# SSTuino_Evo.net
KiCad netlist of a schematic drawn in EAGLE
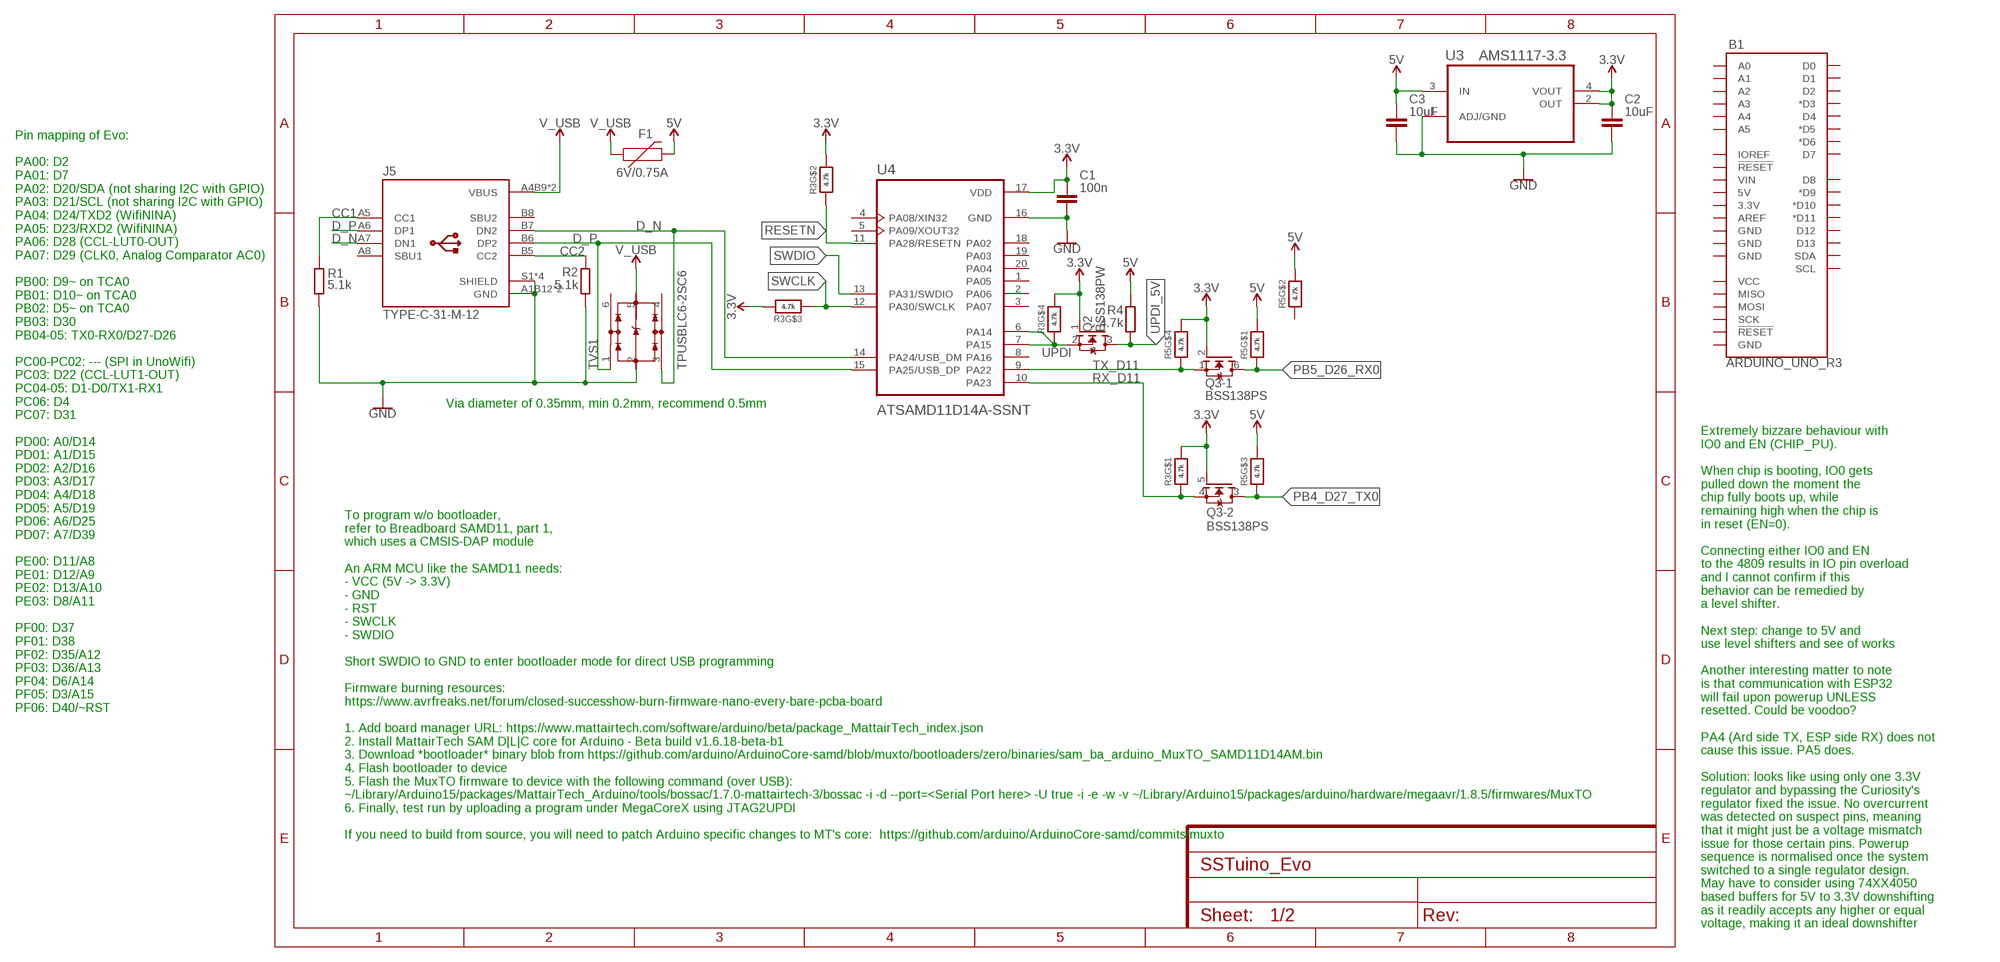
[diagram p0: schematic, sheet 1]
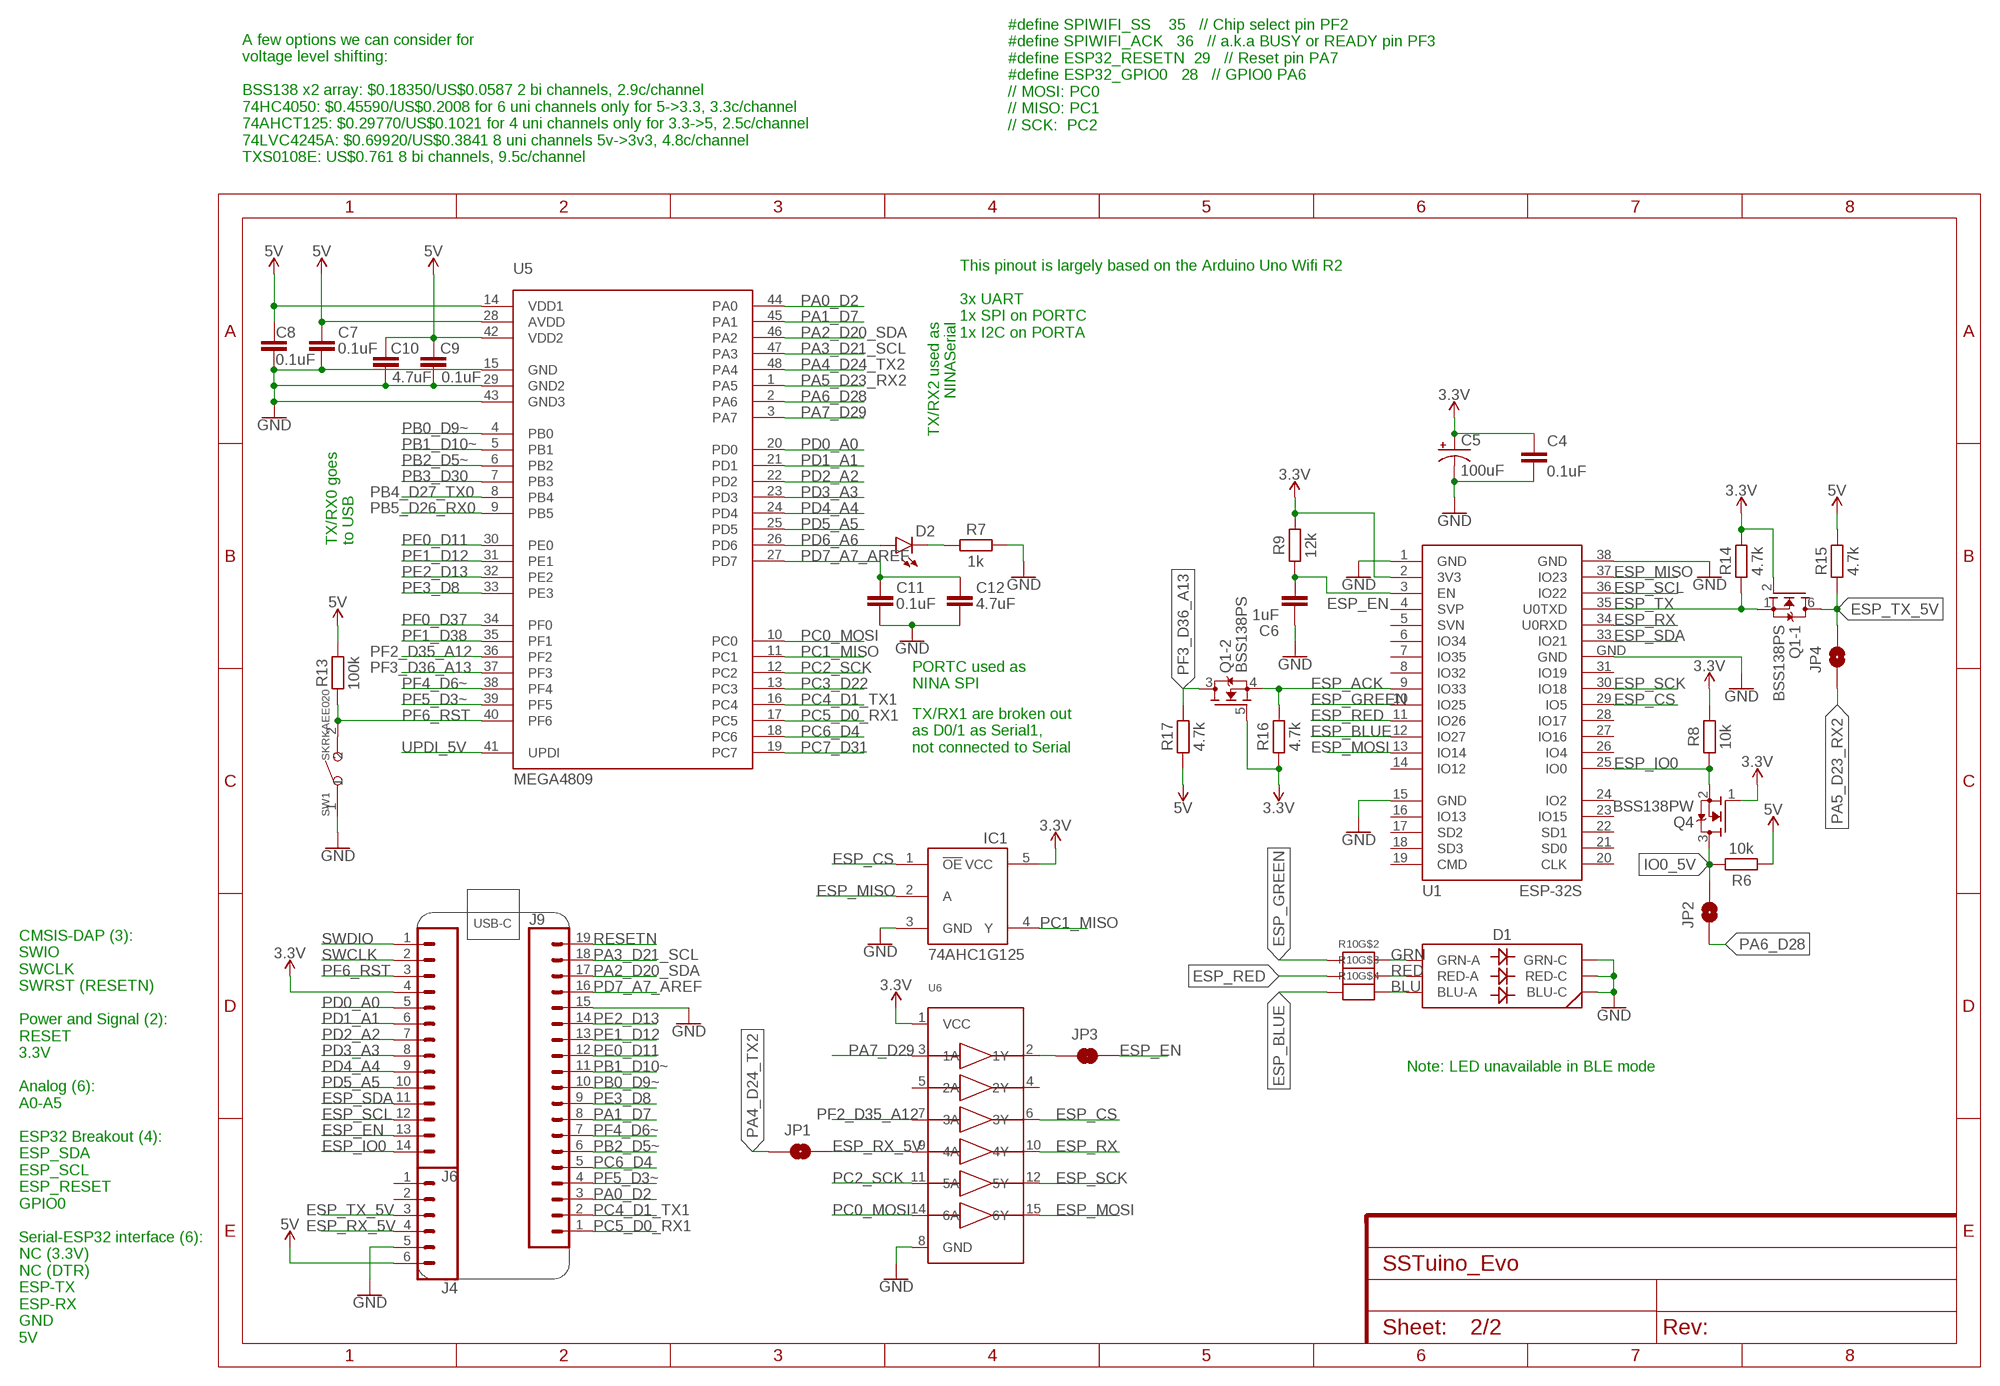
[diagram p1: schematic, sheet 2]

(export (version "E")
  (design (tool "Eeschema 10.0.6"))
  (components
    (comp (ref "B1")
      (value "ARDUINO_UNO_R3")
      (footprint "eagle-import:ARDUINO_R3")
      (libsource (lib "eagle-import") (part "ARDUINO_UNO_R3"))
    )
    (comp (ref "C1")
      (value "100n")
      (footprint "eagle-import:CAPC1005X60")
      (libsource (lib "eagle-import") (part "CCHIP-0402(1005-METRIC)_"))
    )
    (comp (ref "C2")
      (value "10uF")
      (footprint "eagle-import:CAPC1608X85")
      (libsource (lib "eagle-import") (part "CCHIP-0603(1608-METRIC)_"))
    )
    (comp (ref "C3")
      (value "10uF")
      (footprint "eagle-import:CAPC1608X85")
      (libsource (lib "eagle-import") (part "CCHIP-0603(1608-METRIC)_"))
    )
    (comp (ref "F1")
      (value "6V/0.75A")
      (footprint "eagle-import:1206")
      (fields (field (name "LCSC_PART") "C99563"))
      (libsource (lib "eagle-import") (part "PPTC_THREE-QUARTER-AMP"))
    )
    (comp (ref "J5")
      (value "TYPE-C-31-M-12")
      (footprint "eagle-import:HRO_TYPE-C-31-M-12")
      (fields (field (name "MF") "HRO Electronics Co., Ltd.") (field (name "LCSC_PART") "C165948"))
      (libsource (lib "eagle-import") (part "TYPE-C-31-M-12"))
    )
    (comp (ref "Q2")
      (value "BSS138PW")
      (footprint "eagle-import:SOT65P210X110-3N")
      (fields (field (name "MF") "NXP Semiconductors"))
      (libsource (lib "eagle-import") (part "BSS138PW"))
    )
    (comp (ref "Q3")
      (value "BSS138PS")
      (footprint "eagle-import:ARDUINO-TRANSISTORS_SOT363")
      (fields (field (name "MANUFACTURER") "NXP") (field (name "LCSC_PART") "C193381"))
      (libsource (lib "eagle-import") (part "BSS138PS"))
    )
    (comp (ref "R1")
      (value "5.1k")
      (footprint "eagle-import:RESC1005X40")
      (libsource (lib "eagle-import") (part "RCHIP-0402(1005-METRIC)_"))
    )
    (comp (ref "R2")
      (value "5.1k")
      (footprint "eagle-import:RESC1005X40")
      (libsource (lib "eagle-import") (part "RCHIP-0402(1005-METRIC)_"))
    )
    (comp (ref "R3")
      (value "4.7k")
      (footprint "eagle-import:RESPACK_4X0402")
      (fields (field (name "LCSC_PART") "C1980"))
      (libsource (lib "eagle-import") (part "RESISTOR_4PACK0402"))
    )
    (comp (ref "R4")
      (value "4.7k")
      (footprint "eagle-import:RESC1005X40")
      (libsource (lib "eagle-import") (part "RCHIP-0402(1005-METRIC)_"))
    )
    (comp (ref "R5")
      (value "4.7k")
      (footprint "eagle-import:RESPACK_4X0402")
      (fields (field (name "LCSC_PART") "C1980"))
      (libsource (lib "eagle-import") (part "RESISTOR_4PACK0402"))
    )
    (comp (ref "TVS1")
      (value "TPUSBLC6-2SC6")
      (footprint "eagle-import:SOT95P280X110-6N")
      (fields (field (name "LCSC_PART") "C558442"))
      (libsource (lib "eagle-import") (part "TPUSBLC6-2SC6"))
    )
    (comp (ref "U3")
      (value "AMS1117-3.3")
      (footprint "eagle-import:SOT230P696X180-4N")
      (fields (field (name "MPN") "LM1117MP-3.3") (field (name "LCSC_PART") "C6186"))
      (libsource (lib "eagle-import") (part "LM1117MP-3.3"))
    )
    (comp (ref "U4")
      (value "ATSAMD11D14A-SSNT")
      (footprint "eagle-import:SOIC127P1030X265-20N")
      (fields (field (name "MF") "Microchip") (field (name "LCSC_PART") "C2053599"))
      (libsource (lib "eagle-import") (part "ATSAMD11D14A-SSNT"))
    )
    (comp (ref "C4")
      (value "0.1uF")
      (footprint "eagle-import:CAPC1005X60")
      (libsource (lib "eagle-import") (part "CCHIP-0402(1005-METRIC)_"))
    )
    (comp (ref "C5")
      (value "100uF")
      (footprint "eagle-import:CAPMP3216X180N")
      (libsource (lib "eagle-import") (part "C-POL-USTANTALUM-1206(3216-METRIC)_"))
    )
    (comp (ref "C6")
      (value "1uF")
      (footprint "eagle-import:CAPC1005X60")
      (libsource (lib "eagle-import") (part "CCHIP-0402(1005-METRIC)_"))
    )
    (comp (ref "C7")
      (value "0.1uF")
      (footprint "eagle-import:CAPC1005X60")
      (libsource (lib "eagle-import") (part "CCHIP-0402(1005-METRIC)_"))
    )
    (comp (ref "C8")
      (value "0.1uF")
      (footprint "eagle-import:CAPC1005X60")
      (libsource (lib "eagle-import") (part "CCHIP-0402(1005-METRIC)_"))
    )
    (comp (ref "C9")
      (value "0.1uF")
      (footprint "eagle-import:CAPC1005X60")
      (libsource (lib "eagle-import") (part "CCHIP-0402(1005-METRIC)_"))
    )
    (comp (ref "C10")
      (value "4.7uF")
      (footprint "eagle-import:CAPC1005X60")
      (libsource (lib "eagle-import") (part "CCHIP-0402(1005-METRIC)_"))
    )
    (comp (ref "C11")
      (value "0.1uF")
      (footprint "eagle-import:CAPC1005X60")
      (libsource (lib "eagle-import") (part "CCHIP-0402(1005-METRIC)_"))
    )
    (comp (ref "C12")
      (value "4.7uF")
      (footprint "eagle-import:CAPC1005X60")
      (libsource (lib "eagle-import") (part "CCHIP-0402(1005-METRIC)_"))
    )
    (comp (ref "D1")
      (value "LED-RGBTC5050RGBF08")
      (footprint "eagle-import:LED-TRICOLOR-5050")
      (libsource (lib "eagle-import") (part "LED-RGBTC5050RGBF08"))
    )
    (comp (ref "D2")
      (value "LED0603")
      (footprint "eagle-import:LED-0603")
      (libsource (lib "eagle-import") (part "LED0603"))
    )
    (comp (ref "IC1")
      (value "74AHC1G125")
      (footprint "eagle-import:SOT23-5L")
      (fields (field (name "LCSC_PART") "C124295"))
      (libsource (lib "eagle-import") (part "74AHC1G125"))
    )
    (comp (ref "J4")
      (value "CONN_06NO_SILK_FEMALE_PTH")
      (footprint "eagle-import:1X06_NO_SILK")
      (libsource (lib "eagle-import") (part "CONN_06NO_SILK_FEMALE_PTH"))
    )
    (comp (ref "J6")
      (value "CONN_14NO_SILK")
      (footprint "eagle-import:1X14_NO_SILK")
      (libsource (lib "eagle-import") (part "CONN_14NO_SILK"))
    )
    (comp (ref "J9")
      (value "CONN_191X19_NO_SILK")
      (footprint "eagle-import:1X19_NO_SILK")
      (libsource (lib "eagle-import") (part "CONN_191X19_NO_SILK"))
    )
    (comp (ref "JP1")
      (value "JUMPER-SMT_2_NO_SILK")
      (footprint "eagle-import:SMT-JUMPER_2_NO_SILK")
      (libsource (lib "eagle-import") (part "JUMPER-SMT_2_NO_SILK"))
    )
    (comp (ref "JP2")
      (value "JUMPER-SMT_2_NO_SILK")
      (footprint "eagle-import:SMT-JUMPER_2_NO_SILK")
      (libsource (lib "eagle-import") (part "JUMPER-SMT_2_NO_SILK"))
    )
    (comp (ref "JP3")
      (value "JUMPER-SMT_2_NC_TRACE_SILK")
      (footprint "eagle-import:SMT-JUMPER_2_NC_TRACE_SILK")
      (libsource (lib "eagle-import") (part "JUMPER-SMT_2_NC_TRACE_SILK"))
    )
    (comp (ref "JP4")
      (value "JUMPER-SMT_2_NO_SILK")
      (footprint "eagle-import:SMT-JUMPER_2_NO_SILK")
      (libsource (lib "eagle-import") (part "JUMPER-SMT_2_NO_SILK"))
    )
    (comp (ref "Q1")
      (value "BSS138PS")
      (footprint "eagle-import:ARDUINO-TRANSISTORS_SOT363")
      (fields (field (name "MANUFACTURER") "NXP") (field (name "LCSC_PART") "C193381"))
      (libsource (lib "eagle-import") (part "BSS138PS"))
    )
    (comp (ref "Q4")
      (value "BSS138PW")
      (footprint "eagle-import:SOT65P210X110-3N")
      (fields (field (name "MF") "NXP Semiconductors"))
      (libsource (lib "eagle-import") (part "BSS138PW"))
    )
    (comp (ref "R6")
      (value "10k")
      (footprint "eagle-import:RESC1005X40")
      (libsource (lib "eagle-import") (part "RCHIP-0402(1005-METRIC)_"))
    )
    (comp (ref "R7")
      (value "1k")
      (footprint "eagle-import:RESC1005X40")
      (libsource (lib "eagle-import") (part "RCHIP-0402(1005-METRIC)_"))
    )
    (comp (ref "R8")
      (value "10k")
      (footprint "eagle-import:RESC1005X40")
      (libsource (lib "eagle-import") (part "RCHIP-0402(1005-METRIC)_"))
    )
    (comp (ref "R9")
      (value "12k")
      (footprint "eagle-import:RESC1005X40")
      (libsource (lib "eagle-import") (part "RCHIP-0402(1005-METRIC)_"))
    )
    (comp (ref "R10")
      (value "RESISTOR_4PACK0402")
      (footprint "eagle-import:RESPACK_4X0402")
      (libsource (lib "eagle-import") (part "RESISTOR_4PACK0402"))
    )
    (comp (ref "R13")
      (value "100k")
      (footprint "eagle-import:RESC1005X40")
      (libsource (lib "eagle-import") (part "RCHIP-0402(1005-METRIC)_"))
    )
    (comp (ref "R14")
      (value "4.7k")
      (footprint "eagle-import:RESC1005X40")
      (libsource (lib "eagle-import") (part "RCHIP-0402(1005-METRIC)_"))
    )
    (comp (ref "R15")
      (value "4.7k")
      (footprint "eagle-import:RESC1005X40")
      (libsource (lib "eagle-import") (part "RCHIP-0402(1005-METRIC)_"))
    )
    (comp (ref "R16")
      (value "4.7k")
      (footprint "eagle-import:RESC1005X40")
      (libsource (lib "eagle-import") (part "RCHIP-0402(1005-METRIC)_"))
    )
    (comp (ref "R17")
      (value "4.7k")
      (footprint "eagle-import:RESC1005X40")
      (libsource (lib "eagle-import") (part "RCHIP-0402(1005-METRIC)_"))
    )
    (comp (ref "SW1")
      (value "SKRKAEE020")
      (footprint "eagle-import:SW2-2.6-3.9X2.9X1.5+0.4MM")
      (fields (field (name "LCSC_PART") "C115357") (field (name "LCSC_PART_1") "C115357"))
      (libsource (lib "eagle-import") (part "SMD-BUTTON(2P-3.9X2.9X1.5+0.4MM)-SKRKAEE020"))
    )
    (comp (ref "U1")
      (value "ESP-32S")
      (footprint "eagle-import:ESP-32S")
      (libsource (lib "eagle-import") (part "ESP-32S"))
    )
    (comp (ref "U5")
      (value "MEGA4809")
      (footprint "eagle-import:TQFP48")
      (fields (field (name "LCSC_PART") "C189475"))
      (libsource (lib "eagle-import") (part "MEGA4809"))
    )
    (comp (ref "U6")
      (value "74HC4050DTSSOP")
      (footprint "eagle-import:TSSOP16")
      (fields (field (name "LCSC_PART") "C352825"))
      (libsource (lib "eagle-import") (part "74HC4050DTSSOP"))
    )
  )
  (nets
    (net (code "1") (name "3.3V") (class "Default")
      (node (ref "C1") (pin "1") (pinfunction "1_1") (pintype "passive"))
      (node (ref "C2") (pin "1") (pinfunction "1_1") (pintype "passive"))
      (node (ref "C4") (pin "1") (pinfunction "1_1") (pintype "passive"))
      (node (ref "C5") (pin "1") (pinfunction "+_1") (pintype "passive"))
      (node (ref "IC1") (pin "5") (pinfunction "VCC_5") (pintype "power_in"))
      (node (ref "J6") (pin "4") (pinfunction "4_4") (pintype "passive"))
      (node (ref "Q1") (pin "2") (pinfunction "G_2") (pintype "passive"))
      (node (ref "Q1") (pin "5") (pinfunction "G_5") (pintype "passive"))
      (node (ref "Q2") (pin "1") (pinfunction "G_1") (pintype "passive"))
      (node (ref "Q3") (pin "2") (pinfunction "G_2") (pintype "passive"))
      (node (ref "Q3") (pin "5") (pinfunction "G_5") (pintype "passive"))
      (node (ref "Q4") (pin "1") (pinfunction "G_1") (pintype "passive"))
      (node (ref "R14") (pin "2") (pinfunction "2_2") (pintype "passive"))
      (node (ref "R16") (pin "1") (pinfunction "1_1") (pintype "passive"))
      (node (ref "R3") (pin "5") (pinfunction "2_5") (pintype "passive"))
      (node (ref "R3") (pin "6") (pinfunction "2_6") (pintype "passive"))
      (node (ref "R3") (pin "7") (pinfunction "2_7") (pintype "passive"))
      (node (ref "R3") (pin "8") (pinfunction "2_8") (pintype "passive"))
      (node (ref "R5") (pin "5") (pinfunction "2_5") (pintype "passive"))
      (node (ref "R8") (pin "2") (pinfunction "2_2") (pintype "passive"))
      (node (ref "R9") (pin "2") (pinfunction "2_2") (pintype "passive"))
      (node (ref "U1") (pin "2") (pinfunction "3V3_2") (pintype "power_in"))
      (node (ref "U3") (pin "2") (pinfunction "OUT_2") (pintype "output"))
      (node (ref "U3") (pin "4") (pinfunction "VOUT_4") (pintype "output"))
      (node (ref "U4") (pin "17") (pinfunction "VDD_17") (pintype "power_in"))
      (node (ref "U6") (pin "1") (pinfunction "VCC_1") (pintype "bidirectional"))
    )
    (net (code "2") (name "5V") (class "Default")
      (node (ref "C10") (pin "1") (pinfunction "1_1") (pintype "passive"))
      (node (ref "C3") (pin "1") (pinfunction "1_1") (pintype "passive"))
      (node (ref "C7") (pin "1") (pinfunction "1_1") (pintype "passive"))
      (node (ref "C8") (pin "1") (pinfunction "1_1") (pintype "passive"))
      (node (ref "C9") (pin "1") (pinfunction "1_1") (pintype "passive"))
      (node (ref "F1") (pin "2") (pinfunction "2_2") (pintype "bidirectional"))
      (node (ref "J4") (pin "6") (pinfunction "6_6") (pintype "passive"))
      (node (ref "R13") (pin "2") (pinfunction "2_2") (pintype "passive"))
      (node (ref "R15") (pin "2") (pinfunction "2_2") (pintype "passive"))
      (node (ref "R17") (pin "1") (pinfunction "1_1") (pintype "passive"))
      (node (ref "R4") (pin "2") (pinfunction "2_2") (pintype "passive"))
      (node (ref "R5") (pin "6") (pinfunction "2_6") (pintype "passive"))
      (node (ref "R5") (pin "7") (pinfunction "2_7") (pintype "passive"))
      (node (ref "R5") (pin "8") (pinfunction "2_8") (pintype "passive"))
      (node (ref "R6") (pin "1") (pinfunction "1_1") (pintype "passive"))
      (node (ref "U3") (pin "3") (pinfunction "IN_3") (pintype "input"))
      (node (ref "U5") (pin "14") (pinfunction "VDD1_14") (pintype "bidirectional"))
      (node (ref "U5") (pin "28") (pinfunction "AVDD_28") (pintype "bidirectional"))
      (node (ref "U5") (pin "42") (pinfunction "VDD2_42") (pintype "bidirectional"))
    )
    (net (code "3") (name "BLU") (class "Default")
      (node (ref "D1") (pin "6") (pinfunction "BLU-A_6") (pintype "bidirectional"))
      (node (ref "R10") (pin "5") (pinfunction "2_5") (pintype "passive"))
    )
    (net (code "4") (name "CC1") (class "Default")
      (node (ref "J5") (pin "A5") (pinfunction "CC1_A5") (pintype "bidirectional"))
      (node (ref "R1") (pin "1") (pinfunction "1_1") (pintype "passive"))
    )
    (net (code "5") (name "CC2") (class "Default")
      (node (ref "J5") (pin "B5") (pinfunction "CC2_B5") (pintype "bidirectional"))
      (node (ref "R2") (pin "2") (pinfunction "2_2") (pintype "passive"))
    )
    (net (code "6") (name "D_N") (class "Default")
      (node (ref "J5") (pin "A7") (pinfunction "DN1_A7") (pintype "bidirectional"))
      (node (ref "J5") (pin "B7") (pinfunction "DN2_B7") (pintype "bidirectional"))
      (node (ref "TVS1") (pin "3") (pinfunction "IO2_3") (pintype "passive"))
      (node (ref "U4") (pin "14") (pinfunction "PA24/USB_DM_14") (pintype "bidirectional"))
    )
    (net (code "7") (name "D_P") (class "Default")
      (node (ref "J5") (pin "A6") (pinfunction "DP1_A6") (pintype "bidirectional"))
      (node (ref "J5") (pin "B6") (pinfunction "DP2_B6") (pintype "bidirectional"))
      (node (ref "TVS1") (pin "1") (pinfunction "IO1_1") (pintype "passive"))
      (node (ref "U4") (pin "15") (pinfunction "PA25/USB_DP_15") (pintype "bidirectional"))
    )
    (net (code "8") (name "ESP_ACK") (class "Default")
      (node (ref "Q1") (pin "4") (pinfunction "S_4") (pintype "passive"))
      (node (ref "R16") (pin "2") (pinfunction "2_2") (pintype "passive"))
      (node (ref "U1") (pin "9") (pinfunction "IO33_9") (pintype "bidirectional"))
    )
    (net (code "9") (name "ESP_BLUE") (class "Default")
      (node (ref "R10") (pin "4") (pinfunction "1_4") (pintype "passive"))
      (node (ref "U1") (pin "12") (pinfunction "IO27_12") (pintype "bidirectional"))
    )
    (net (code "10") (name "ESP_CS") (class "Default")
      (node (ref "IC1") (pin "1") (pinfunction "~{OE}_1") (pintype "input"))
      (node (ref "U1") (pin "29") (pinfunction "IO5_29") (pintype "bidirectional"))
      (node (ref "U6") (pin "6") (pinfunction "3Y_6") (pintype "bidirectional"))
    )
    (net (code "11") (name "ESP_EN") (class "Default")
      (node (ref "C6") (pin "2") (pinfunction "2_2") (pintype "passive"))
      (node (ref "J6") (pin "13") (pinfunction "13_13") (pintype "passive"))
      (node (ref "JP3") (pin "2") (pinfunction "2_2") (pintype "passive"))
      (node (ref "R9") (pin "1") (pinfunction "1_1") (pintype "passive"))
      (node (ref "U1") (pin "3") (pinfunction "EN_3") (pintype "input"))
    )
    (net (code "12") (name "ESP_GREEN") (class "Default")
      (node (ref "R10") (pin "2") (pinfunction "1_2") (pintype "passive"))
      (node (ref "U1") (pin "10") (pinfunction "IO25_10") (pintype "bidirectional"))
    )
    (net (code "13") (name "ESP_IO0") (class "Default")
      (node (ref "J6") (pin "14") (pinfunction "14_14") (pintype "passive"))
      (node (ref "Q4") (pin "2") (pinfunction "S_2") (pintype "passive"))
      (node (ref "R8") (pin "1") (pinfunction "1_1") (pintype "passive"))
      (node (ref "U1") (pin "25") (pinfunction "IO0_25") (pintype "bidirectional"))
    )
    (net (code "14") (name "ESP_MISO") (class "Default")
      (node (ref "IC1") (pin "2") (pinfunction "A_2") (pintype "input"))
      (node (ref "U1") (pin "37") (pinfunction "IO23_37") (pintype "bidirectional"))
    )
    (net (code "15") (name "ESP_MOSI") (class "Default")
      (node (ref "U1") (pin "13") (pinfunction "IO14_13") (pintype "bidirectional"))
      (node (ref "U6") (pin "15") (pinfunction "6Y_15") (pintype "bidirectional"))
    )
    (net (code "16") (name "ESP_RED") (class "Default")
      (node (ref "R10") (pin "3") (pinfunction "1_3") (pintype "passive"))
      (node (ref "U1") (pin "11") (pinfunction "IO26_11") (pintype "bidirectional"))
    )
    (net (code "17") (name "ESP_RX") (class "Default")
      (node (ref "U1") (pin "34") (pinfunction "U0RXD_34") (pintype "bidirectional"))
      (node (ref "U6") (pin "10") (pinfunction "4Y_10") (pintype "bidirectional"))
    )
    (net (code "18") (name "ESP_RX_5V") (class "Default")
      (node (ref "J4") (pin "4") (pinfunction "4_4") (pintype "passive"))
      (node (ref "JP1") (pin "2") (pinfunction "2_2") (pintype "passive"))
      (node (ref "U6") (pin "9") (pinfunction "4A_9") (pintype "bidirectional"))
    )
    (net (code "19") (name "ESP_SCK") (class "Default")
      (node (ref "U1") (pin "30") (pinfunction "IO18_30") (pintype "bidirectional"))
      (node (ref "U6") (pin "12") (pinfunction "5Y_12") (pintype "bidirectional"))
    )
    (net (code "20") (name "ESP_SCL") (class "Default")
      (node (ref "J6") (pin "12") (pinfunction "12_12") (pintype "passive"))
      (node (ref "U1") (pin "36") (pinfunction "IO22_36") (pintype "bidirectional"))
    )
    (net (code "21") (name "ESP_SDA") (class "Default")
      (node (ref "J6") (pin "11") (pinfunction "11_11") (pintype "passive"))
      (node (ref "U1") (pin "33") (pinfunction "IO21_33") (pintype "bidirectional"))
    )
    (net (code "22") (name "ESP_TX") (class "Default")
      (node (ref "Q1") (pin "1") (pinfunction "S_1") (pintype "passive"))
      (node (ref "R14") (pin "1") (pinfunction "1_1") (pintype "passive"))
      (node (ref "U1") (pin "35") (pinfunction "U0TXD_35") (pintype "bidirectional"))
    )
    (net (code "23") (name "ESP_TX_5V") (class "Default")
      (node (ref "J4") (pin "3") (pinfunction "3_3") (pintype "passive"))
      (node (ref "JP4") (pin "2") (pinfunction "2_2") (pintype "passive"))
      (node (ref "Q1") (pin "6") (pinfunction "D_6") (pintype "passive"))
      (node (ref "R15") (pin "1") (pinfunction "1_1") (pintype "passive"))
    )
    (net (code "24") (name "GND") (class "Default")
      (node (ref "C1") (pin "2") (pinfunction "2_2") (pintype "passive"))
      (node (ref "C10") (pin "2") (pinfunction "2_2") (pintype "passive"))
      (node (ref "C11") (pin "2") (pinfunction "2_2") (pintype "passive"))
      (node (ref "C12") (pin "2") (pinfunction "2_2") (pintype "passive"))
      (node (ref "C2") (pin "2") (pinfunction "2_2") (pintype "passive"))
      (node (ref "C3") (pin "2") (pinfunction "2_2") (pintype "passive"))
      (node (ref "C4") (pin "2") (pinfunction "2_2") (pintype "passive"))
      (node (ref "C5") (pin "2") (pinfunction "-_2") (pintype "passive"))
      (node (ref "C6") (pin "1") (pinfunction "1_1") (pintype "passive"))
      (node (ref "C7") (pin "2") (pinfunction "2_2") (pintype "passive"))
      (node (ref "C8") (pin "2") (pinfunction "2_2") (pintype "passive"))
      (node (ref "C9") (pin "2") (pinfunction "2_2") (pintype "passive"))
      (node (ref "D1") (pin "1") (pinfunction "BLU-C_1") (pintype "bidirectional"))
      (node (ref "D1") (pin "2") (pinfunction "RED-C_2") (pintype "bidirectional"))
      (node (ref "D1") (pin "3") (pinfunction "GRN-C_3") (pintype "bidirectional"))
      (node (ref "IC1") (pin "3") (pinfunction "GND_3") (pintype "power_in"))
      (node (ref "J4") (pin "5") (pinfunction "5_5") (pintype "passive"))
      (node (ref "J5") (pin "A1B12") (pinfunction "GND_A1B12") (pintype "power_in"))
      (node (ref "J5") (pin "B1A12") (pinfunction "GND_B1A12") (pintype "power_in"))
      (node (ref "J5") (pin "S1") (pinfunction "SHIELD_S1") (pintype "passive"))
      (node (ref "J5") (pin "S2") (pinfunction "SHIELD_S2") (pintype "passive"))
      (node (ref "J5") (pin "S3") (pinfunction "SHIELD_S3") (pintype "passive"))
      (node (ref "J5") (pin "S4") (pinfunction "SHIELD_S4") (pintype "passive"))
      (node (ref "J9") (pin "15") (pinfunction "15_15") (pintype "passive"))
      (node (ref "R1") (pin "2") (pinfunction "2_2") (pintype "passive"))
      (node (ref "R2") (pin "1") (pinfunction "1_1") (pintype "passive"))
      (node (ref "R7") (pin "2") (pinfunction "2_2") (pintype "passive"))
      (node (ref "SW1") (pin "1") (pinfunction "1_1") (pintype "bidirectional"))
      (node (ref "TVS1") (pin "2") (pinfunction "VSS_2") (pintype "power_in"))
      (node (ref "U1") (pin "1") (pinfunction "GND_1") (pintype "power_in"))
      (node (ref "U1") (pin "15") (pinfunction "GND_15") (pintype "power_in"))
      (node (ref "U1") (pin "38") (pinfunction "GND_38") (pintype "power_in"))
      (node (ref "U1") (pin "GND") (pinfunction "GND_GND") (pintype "power_in"))
      (node (ref "U3") (pin "1") (pinfunction "ADJ/GND_1") (pintype "passive"))
      (node (ref "U4") (pin "16") (pinfunction "GND_16") (pintype "power_in"))
      (node (ref "U5") (pin "15") (pinfunction "GND_15") (pintype "bidirectional"))
      (node (ref "U5") (pin "29") (pinfunction "GND2_29") (pintype "bidirectional"))
      (node (ref "U5") (pin "43") (pinfunction "GND3_43") (pintype "bidirectional"))
      (node (ref "U6") (pin "8") (pinfunction "GND_8") (pintype "bidirectional"))
    )
    (net (code "25") (name "GRN") (class "Default")
      (node (ref "D1") (pin "4") (pinfunction "GRN-A_4") (pintype "bidirectional"))
      (node (ref "R10") (pin "7") (pinfunction "2_7") (pintype "passive"))
    )
    (net (code "26") (name "IO0_5V") (class "Default")
      (node (ref "JP2") (pin "2") (pinfunction "2_2") (pintype "passive"))
      (node (ref "Q4") (pin "3") (pinfunction "D_3") (pintype "passive"))
      (node (ref "R6") (pin "2") (pinfunction "2_2") (pintype "passive"))
    )
    (net (code "27") (name "Net-(D2-PadC)") (class "Default")
      (node (ref "D2") (pin "C") (pinfunction "C_C") (pintype "passive"))
      (node (ref "R7") (pin "1") (pinfunction "1_1") (pintype "passive"))
    )
    (net (code "28") (name "Net-(U6-1Y)") (class "Default")
      (node (ref "JP3") (pin "1") (pinfunction "1_1") (pintype "passive"))
      (node (ref "U6") (pin "2") (pinfunction "1Y_2") (pintype "bidirectional"))
    )
    (net (code "29") (name "PA0_D2") (class "Default")
      (node (ref "J9") (pin "3") (pinfunction "3_3") (pintype "passive"))
      (node (ref "U5") (pin "44") (pinfunction "PA0_44") (pintype "bidirectional"))
    )
    (net (code "30") (name "PA1_D7") (class "Default")
      (node (ref "J9") (pin "8") (pinfunction "8_8") (pintype "passive"))
      (node (ref "U5") (pin "45") (pinfunction "PA1_45") (pintype "bidirectional"))
    )
    (net (code "31") (name "PA2_D20_SDA") (class "Default")
      (node (ref "J9") (pin "17") (pinfunction "17_17") (pintype "passive"))
      (node (ref "U5") (pin "46") (pinfunction "PA2_46") (pintype "bidirectional"))
    )
    (net (code "32") (name "PA3_D21_SCL") (class "Default")
      (node (ref "J9") (pin "18") (pinfunction "18_18") (pintype "passive"))
      (node (ref "U5") (pin "47") (pinfunction "PA3_47") (pintype "bidirectional"))
    )
    (net (code "33") (name "PA4_D24_TX2") (class "Default")
      (node (ref "JP1") (pin "1") (pinfunction "1_1") (pintype "passive"))
      (node (ref "U5") (pin "48") (pinfunction "PA4_48") (pintype "bidirectional"))
    )
    (net (code "34") (name "PA5_D23_RX2") (class "Default")
      (node (ref "JP4") (pin "1") (pinfunction "1_1") (pintype "passive"))
      (node (ref "U5") (pin "1") (pinfunction "PA5_1") (pintype "bidirectional"))
    )
    (net (code "35") (name "PA6_D28") (class "Default")
      (node (ref "JP2") (pin "1") (pinfunction "1_1") (pintype "passive"))
      (node (ref "U5") (pin "2") (pinfunction "PA6_2") (pintype "bidirectional"))
    )
    (net (code "36") (name "PA7_D29") (class "Default")
      (node (ref "U5") (pin "3") (pinfunction "PA7_3") (pintype "bidirectional"))
      (node (ref "U6") (pin "3") (pinfunction "1A_3") (pintype "bidirectional"))
    )
    (net (code "37") (name "PB0_D9~{}") (class "Default")
      (node (ref "J9") (pin "10") (pinfunction "10_10") (pintype "passive"))
      (node (ref "U5") (pin "4") (pinfunction "PB0_4") (pintype "bidirectional"))
    )
    (net (code "38") (name "PB1_D10~{}") (class "Default")
      (node (ref "J9") (pin "11") (pinfunction "11_11") (pintype "passive"))
      (node (ref "U5") (pin "5") (pinfunction "PB1_5") (pintype "bidirectional"))
    )
    (net (code "39") (name "PB2_D5~{}") (class "Default")
      (node (ref "J9") (pin "6") (pinfunction "6_6") (pintype "passive"))
      (node (ref "U5") (pin "6") (pinfunction "PB2_6") (pintype "bidirectional"))
    )
    (net (code "40") (name "PB3_D30") (class "Default")
      (node (ref "U5") (pin "7") (pinfunction "PB3_7") (pintype "bidirectional"))
    )
    (net (code "41") (name "PB4_D27_TX0") (class "Default")
      (node (ref "Q3") (pin "3") (pinfunction "D_3") (pintype "passive"))
      (node (ref "R5") (pin "3") (pinfunction "1_3") (pintype "passive"))
      (node (ref "U5") (pin "8") (pinfunction "PB4_8") (pintype "bidirectional"))
    )
    (net (code "42") (name "PB5_D26_RX0") (class "Default")
      (node (ref "Q3") (pin "6") (pinfunction "D_6") (pintype "passive"))
      (node (ref "R5") (pin "1") (pinfunction "1_1") (pintype "passive"))
      (node (ref "U5") (pin "9") (pinfunction "PB5_9") (pintype "bidirectional"))
    )
    (net (code "43") (name "PC0_MOSI") (class "Default")
      (node (ref "U5") (pin "10") (pinfunction "PC0_10") (pintype "bidirectional"))
      (node (ref "U6") (pin "14") (pinfunction "6A_14") (pintype "bidirectional"))
    )
    (net (code "44") (name "PC1_MISO") (class "Default")
      (node (ref "IC1") (pin "4") (pinfunction "Y_4") (pintype "output"))
      (node (ref "U5") (pin "11") (pinfunction "PC1_11") (pintype "bidirectional"))
    )
    (net (code "45") (name "PC2_SCK") (class "Default")
      (node (ref "U5") (pin "12") (pinfunction "PC2_12") (pintype "bidirectional"))
      (node (ref "U6") (pin "11") (pinfunction "5A_11") (pintype "bidirectional"))
    )
    (net (code "46") (name "PC3_D22") (class "Default")
      (node (ref "U5") (pin "13") (pinfunction "PC3_13") (pintype "bidirectional"))
    )
    (net (code "47") (name "PC4_D1_TX1") (class "Default")
      (node (ref "J9") (pin "2") (pinfunction "2_2") (pintype "passive"))
      (node (ref "U5") (pin "16") (pinfunction "PC4_16") (pintype "bidirectional"))
    )
    (net (code "48") (name "PC5_D0_RX1") (class "Default")
      (node (ref "J9") (pin "1") (pinfunction "1_1") (pintype "passive"))
      (node (ref "U5") (pin "17") (pinfunction "PC5_17") (pintype "bidirectional"))
    )
    (net (code "49") (name "PC6_D4") (class "Default")
      (node (ref "J9") (pin "5") (pinfunction "5_5") (pintype "passive"))
      (node (ref "U5") (pin "18") (pinfunction "PC6_18") (pintype "bidirectional"))
    )
    (net (code "50") (name "PC7_D31") (class "Default")
      (node (ref "U5") (pin "19") (pinfunction "PC7_19") (pintype "bidirectional"))
    )
    (net (code "51") (name "PD0_A0") (class "Default")
      (node (ref "J6") (pin "5") (pinfunction "5_5") (pintype "passive"))
      (node (ref "U5") (pin "20") (pinfunction "PD0_20") (pintype "bidirectional"))
    )
    (net (code "52") (name "PD1_A1") (class "Default")
      (node (ref "J6") (pin "6") (pinfunction "6_6") (pintype "passive"))
      (node (ref "U5") (pin "21") (pinfunction "PD1_21") (pintype "bidirectional"))
    )
    (net (code "53") (name "PD2_A2") (class "Default")
      (node (ref "J6") (pin "7") (pinfunction "7_7") (pintype "passive"))
      (node (ref "U5") (pin "22") (pinfunction "PD2_22") (pintype "bidirectional"))
    )
    (net (code "54") (name "PD3_A3") (class "Default")
      (node (ref "J6") (pin "8") (pinfunction "8_8") (pintype "passive"))
      (node (ref "U5") (pin "23") (pinfunction "PD3_23") (pintype "bidirectional"))
    )
    (net (code "55") (name "PD4_A4") (class "Default")
      (node (ref "J6") (pin "9") (pinfunction "9_9") (pintype "passive"))
      (node (ref "U5") (pin "24") (pinfunction "PD4_24") (pintype "bidirectional"))
    )
    (net (code "56") (name "PD5_A5") (class "Default")
      (node (ref "J6") (pin "10") (pinfunction "10_10") (pintype "passive"))
      (node (ref "U5") (pin "25") (pinfunction "PD5_25") (pintype "bidirectional"))
    )
    (net (code "57") (name "PD6_A6") (class "Default")
      (node (ref "D2") (pin "A") (pinfunction "A_A") (pintype "passive"))
      (node (ref "U5") (pin "26") (pinfunction "PD6_26") (pintype "bidirectional"))
    )
    (net (code "58") (name "PD7_A7_AREF") (class "Default")
      (node (ref "C11") (pin "1") (pinfunction "1_1") (pintype "passive"))
      (node (ref "C12") (pin "1") (pinfunction "1_1") (pintype "passive"))
      (node (ref "J9") (pin "16") (pinfunction "16_16") (pintype "passive"))
      (node (ref "U5") (pin "27") (pinfunction "PD7_27") (pintype "bidirectional"))
    )
    (net (code "59") (name "PE0_D11") (class "Default")
      (node (ref "J9") (pin "12") (pinfunction "12_12") (pintype "passive"))
      (node (ref "U5") (pin "30") (pinfunction "PE0_30") (pintype "bidirectional"))
    )
    (net (code "60") (name "PE1_D12") (class "Default")
      (node (ref "J9") (pin "13") (pinfunction "13_13") (pintype "passive"))
      (node (ref "U5") (pin "31") (pinfunction "PE1_31") (pintype "bidirectional"))
    )
    (net (code "61") (name "PE2_D13") (class "Default")
      (node (ref "J9") (pin "14") (pinfunction "14_14") (pintype "passive"))
      (node (ref "U5") (pin "32") (pinfunction "PE2_32") (pintype "bidirectional"))
    )
    (net (code "62") (name "PE3_D8") (class "Default")
      (node (ref "J9") (pin "9") (pinfunction "9_9") (pintype "passive"))
      (node (ref "U5") (pin "33") (pinfunction "PE3_33") (pintype "bidirectional"))
    )
    (net (code "63") (name "PF0_D37") (class "Default")
      (node (ref "U5") (pin "34") (pinfunction "PF0_34") (pintype "bidirectional"))
    )
    (net (code "64") (name "PF1_D38") (class "Default")
      (node (ref "U5") (pin "35") (pinfunction "PF1_35") (pintype "bidirectional"))
    )
    (net (code "65") (name "PF2_D35_A12") (class "Default")
      (node (ref "U5") (pin "36") (pinfunction "PF2_36") (pintype "bidirectional"))
      (node (ref "U6") (pin "7") (pinfunction "3A_7") (pintype "bidirectional"))
    )
    (net (code "66") (name "PF3_D36_A13") (class "Default")
      (node (ref "Q1") (pin "3") (pinfunction "D_3") (pintype "passive"))
      (node (ref "R17") (pin "2") (pinfunction "2_2") (pintype "passive"))
      (node (ref "U5") (pin "37") (pinfunction "PF3_37") (pintype "bidirectional"))
    )
    (net (code "67") (name "PF4_D6~{}") (class "Default")
      (node (ref "J9") (pin "7") (pinfunction "7_7") (pintype "passive"))
      (node (ref "U5") (pin "38") (pinfunction "PF4_38") (pintype "bidirectional"))
    )
    (net (code "68") (name "PF5_D3~{}") (class "Default")
      (node (ref "J9") (pin "4") (pinfunction "4_4") (pintype "passive"))
      (node (ref "U5") (pin "39") (pinfunction "PF5_39") (pintype "bidirectional"))
    )
    (net (code "69") (name "PF6_RST") (class "Default")
      (node (ref "J6") (pin "3") (pinfunction "3_3") (pintype "passive"))
      (node (ref "R13") (pin "1") (pinfunction "1_1") (pintype "passive"))
      (node (ref "SW1") (pin "2") (pinfunction "2_2") (pintype "bidirectional"))
      (node (ref "U5") (pin "40") (pinfunction "PF6_40") (pintype "bidirectional"))
    )
    (net (code "70") (name "RED") (class "Default")
      (node (ref "D1") (pin "5") (pinfunction "RED-A_5") (pintype "bidirectional"))
      (node (ref "R10") (pin "6") (pinfunction "2_6") (pintype "passive"))
    )
    (net (code "71") (name "RESETN") (class "Default")
      (node (ref "J9") (pin "19") (pinfunction "19_19") (pintype "passive"))
      (node (ref "R3") (pin "2") (pinfunction "1_2") (pintype "passive"))
      (node (ref "U4") (pin "11") (pinfunction "PA28/RESETN_11") (pintype "input"))
    )
    (net (code "72") (name "RX_D11") (class "Default")
      (node (ref "Q3") (pin "4") (pinfunction "S_4") (pintype "passive"))
      (node (ref "R3") (pin "1") (pinfunction "1_1") (pintype "passive"))
      (node (ref "U4") (pin "10") (pinfunction "PA23_10") (pintype "bidirectional"))
    )
    (net (code "73") (name "SWCLK") (class "Default")
      (node (ref "J6") (pin "2") (pinfunction "2_2") (pintype "passive"))
      (node (ref "R3") (pin "3") (pinfunction "1_3") (pintype "passive"))
      (node (ref "U4") (pin "12") (pinfunction "PA30/SWCLK_12") (pintype "bidirectional"))
    )
    (net (code "74") (name "SWDIO") (class "Default")
      (node (ref "J6") (pin "1") (pinfunction "1_1") (pintype "passive"))
      (node (ref "U4") (pin "13") (pinfunction "PA31/SWDIO_13") (pintype "bidirectional"))
    )
    (net (code "75") (name "TX_D11") (class "Default")
      (node (ref "Q3") (pin "1") (pinfunction "S_1") (pintype "passive"))
      (node (ref "R5") (pin "4") (pinfunction "1_4") (pintype "passive"))
      (node (ref "U4") (pin "9") (pinfunction "PA22_9") (pintype "bidirectional"))
    )
    (net (code "76") (name "UPDI") (class "Default")
      (node (ref "Q2") (pin "2") (pinfunction "S_2") (pintype "passive"))
      (node (ref "R3") (pin "4") (pinfunction "1_4") (pintype "passive"))
      (node (ref "U4") (pin "6") (pinfunction "PA14_6") (pintype "bidirectional"))
      (node (ref "U4") (pin "7") (pinfunction "PA15_7") (pintype "bidirectional"))
    )
    (net (code "77") (name "UPDI_5V") (class "Default")
      (node (ref "Q2") (pin "3") (pinfunction "D_3") (pintype "passive"))
      (node (ref "R4") (pin "1") (pinfunction "1_1") (pintype "passive"))
      (node (ref "U5") (pin "41") (pinfunction "UPDI_41") (pintype "bidirectional"))
    )
    (net (code "78") (name "V_USB") (class "Default")
      (node (ref "F1") (pin "1") (pinfunction "1_1") (pintype "bidirectional"))
      (node (ref "J5") (pin "A4B9") (pinfunction "VBUS_A4B9") (pintype "power_in"))
      (node (ref "J5") (pin "B4A9") (pinfunction "VBUS_B4A9") (pintype "power_in"))
      (node (ref "TVS1") (pin "5") (pinfunction "VCC_5") (pintype "power_in"))
    )
    (net (code "79") (name "unconnected-(B1-*D3-PadD3)") (class "Default")
      (node (ref "B1") (pin "D3") (pinfunction "*D3_D3") (pintype "bidirectional"))
    )
    (net (code "80") (name "unconnected-(B1-*D5-PadD5)") (class "Default")
      (node (ref "B1") (pin "D5") (pinfunction "*D5_D5") (pintype "bidirectional"))
    )
    (net (code "81") (name "unconnected-(B1-*D6-PadD6)") (class "Default")
      (node (ref "B1") (pin "D6") (pinfunction "*D6_D6") (pintype "bidirectional"))
    )
    (net (code "82") (name "unconnected-(B1-*D9-PadD9)") (class "Default")
      (node (ref "B1") (pin "D9") (pinfunction "*D9_D9") (pintype "bidirectional"))
    )
    (net (code "83") (name "unconnected-(B1-*D10-PadD10)") (class "Default")
      (node (ref "B1") (pin "D10") (pinfunction "*D10_D10") (pintype "bidirectional"))
    )
    (net (code "84") (name "unconnected-(B1-*D11-PadD11)") (class "Default")
      (node (ref "B1") (pin "D11") (pinfunction "*D11_D11") (pintype "bidirectional"))
    )
    (net (code "85") (name "unconnected-(B1-GND-PadGND@1)") (class "Default")
      (node (ref "B1") (pin "GND@1") (pinfunction "GND_GND@1") (pintype "bidirectional"))
    )
    (net (code "86") (name "unconnected-(B1-GND-PadGND@2)") (class "Default")
      (node (ref "B1") (pin "GND@2") (pinfunction "GND_GND@2") (pintype "bidirectional"))
    )
    (net (code "87") (name "unconnected-(B1-GND-PadGND@3)") (class "Default")
      (node (ref "B1") (pin "GND@3") (pinfunction "GND_GND@3") (pintype "bidirectional"))
    )
    (net (code "88") (name "unconnected-(B1-GND-PadGND@4)") (class "Default")
      (node (ref "B1") (pin "GND@4") (pinfunction "GND_GND@4") (pintype "bidirectional"))
    )
    (net (code "89") (name "unconnected-(B1-Pad3.3V)") (class "Default")
      (node (ref "B1") (pin "3.3V") (pinfunction "3.3V_3.3V") (pintype "bidirectional"))
    )
    (net (code "90") (name "unconnected-(B1-Pad5V)") (class "Default")
      (node (ref "B1") (pin "5V") (pinfunction "5V_5V") (pintype "bidirectional"))
    )
    (net (code "91") (name "unconnected-(B1-PadA0)") (class "Default")
      (node (ref "B1") (pin "A0") (pinfunction "A0_A0") (pintype "bidirectional"))
    )
    (net (code "92") (name "unconnected-(B1-PadA1)") (class "Default")
      (node (ref "B1") (pin "A1") (pinfunction "A1_A1") (pintype "bidirectional"))
    )
    (net (code "93") (name "unconnected-(B1-PadA2)") (class "Default")
      (node (ref "B1") (pin "A2") (pinfunction "A2_A2") (pintype "bidirectional"))
    )
    (net (code "94") (name "unconnected-(B1-PadA3)") (class "Default")
      (node (ref "B1") (pin "A3") (pinfunction "A3_A3") (pintype "bidirectional"))
    )
    (net (code "95") (name "unconnected-(B1-PadA4)") (class "Default")
      (node (ref "B1") (pin "A4") (pinfunction "A4_A4") (pintype "bidirectional"))
    )
    (net (code "96") (name "unconnected-(B1-PadA5)") (class "Default")
      (node (ref "B1") (pin "A5") (pinfunction "A5_A5") (pintype "bidirectional"))
    )
    (net (code "97") (name "unconnected-(B1-PadAREF)") (class "Default")
      (node (ref "B1") (pin "AREF") (pinfunction "AREF_AREF") (pintype "bidirectional"))
    )
    (net (code "98") (name "unconnected-(B1-PadD0)") (class "Default")
      (node (ref "B1") (pin "D0") (pinfunction "D0_D0") (pintype "bidirectional"))
    )
    (net (code "99") (name "unconnected-(B1-PadD1)") (class "Default")
      (node (ref "B1") (pin "D1") (pinfunction "D1_D1") (pintype "bidirectional"))
    )
    (net (code "100") (name "unconnected-(B1-PadD2)") (class "Default")
      (node (ref "B1") (pin "D2") (pinfunction "D2_D2") (pintype "bidirectional"))
    )
    (net (code "101") (name "unconnected-(B1-PadD4)") (class "Default")
      (node (ref "B1") (pin "D4") (pinfunction "D4_D4") (pintype "bidirectional"))
    )
    (net (code "102") (name "unconnected-(B1-PadD7)") (class "Default")
      (node (ref "B1") (pin "D7") (pinfunction "D7_D7") (pintype "bidirectional"))
    )
    (net (code "103") (name "unconnected-(B1-PadD8)") (class "Default")
      (node (ref "B1") (pin "D8") (pinfunction "D8_D8") (pintype "bidirectional"))
    )
    (net (code "104") (name "unconnected-(B1-PadD12)") (class "Default")
      (node (ref "B1") (pin "D12") (pinfunction "D12_D12") (pintype "bidirectional"))
    )
    (net (code "105") (name "unconnected-(B1-PadD13)") (class "Default")
      (node (ref "B1") (pin "D13") (pinfunction "D13_D13") (pintype "bidirectional"))
    )
    (net (code "106") (name "unconnected-(B1-PadIOREF)") (class "Default")
      (node (ref "B1") (pin "IOREF") (pinfunction "IOREF_IOREF") (pintype "bidirectional"))
    )
    (net (code "107") (name "unconnected-(B1-PadMISO)") (class "Default")
      (node (ref "B1") (pin "MISO") (pinfunction "MISO_MISO") (pintype "bidirectional"))
    )
    (net (code "108") (name "unconnected-(B1-PadMOSI)") (class "Default")
      (node (ref "B1") (pin "MOSI") (pinfunction "MOSI_MOSI") (pintype "bidirectional"))
    )
    (net (code "109") (name "unconnected-(B1-PadSCK)") (class "Default")
      (node (ref "B1") (pin "SCK") (pinfunction "SCK_SCK") (pintype "bidirectional"))
    )
    (net (code "110") (name "unconnected-(B1-PadSCL)") (class "Default")
      (node (ref "B1") (pin "SCL") (pinfunction "SCL_SCL") (pintype "bidirectional"))
    )
    (net (code "111") (name "unconnected-(B1-PadSDA)") (class "Default")
      (node (ref "B1") (pin "SDA") (pinfunction "SDA_SDA") (pintype "bidirectional"))
    )
    (net (code "112") (name "unconnected-(B1-PadVCC)") (class "Default")
      (node (ref "B1") (pin "VCC") (pinfunction "VCC_VCC") (pintype "bidirectional"))
    )
    (net (code "113") (name "unconnected-(B1-PadVIN)") (class "Default")
      (node (ref "B1") (pin "VIN") (pinfunction "VIN_VIN") (pintype "bidirectional"))
    )
    (net (code "114") (name "unconnected-(B1-~{RESET}-PadRESET@1)") (class "Default")
      (node (ref "B1") (pin "RESET@1") (pinfunction "~{RESET}_RESET@1") (pintype "bidirectional"))
    )
    (net (code "115") (name "unconnected-(B1-~{RESET}-PadRESET@2)") (class "Default")
      (node (ref "B1") (pin "RESET@2") (pinfunction "~{RESET}_RESET@2") (pintype "bidirectional"))
    )
    (net (code "116") (name "unconnected-(J4-Pad1)") (class "Default")
      (node (ref "J4") (pin "1") (pinfunction "1_1") (pintype "passive"))
    )
    (net (code "117") (name "unconnected-(J4-Pad2)") (class "Default")
      (node (ref "J4") (pin "2") (pinfunction "2_2") (pintype "passive"))
    )
    (net (code "118") (name "unconnected-(J5-SBU1-PadA8)") (class "Default")
      (node (ref "J5") (pin "A8") (pinfunction "SBU1_A8") (pintype "bidirectional"))
    )
    (net (code "119") (name "unconnected-(J5-SBU2-PadB8)") (class "Default")
      (node (ref "J5") (pin "B8") (pinfunction "SBU2_B8") (pintype "bidirectional"))
    )
    (net (code "120") (name "unconnected-(R5B-1-Pad2)") (class "Default")
      (node (ref "R5") (pin "2") (pinfunction "1_2") (pintype "passive"))
    )
    (net (code "121") (name "unconnected-(TVS1-IO3-Pad4)") (class "Default")
      (node (ref "TVS1") (pin "4") (pinfunction "IO3_4") (pintype "passive"))
    )
    (net (code "122") (name "unconnected-(TVS1-IO4-Pad6)") (class "Default")
      (node (ref "TVS1") (pin "6") (pinfunction "IO4_6") (pintype "passive"))
    )
    (net (code "123") (name "unconnected-(U1-CLK-Pad20)") (class "Default")
      (node (ref "U1") (pin "20") (pinfunction "CLK_20") (pintype "bidirectional"))
    )
    (net (code "124") (name "unconnected-(U1-CMD-Pad19)") (class "Default")
      (node (ref "U1") (pin "19") (pinfunction "CMD_19") (pintype "bidirectional"))
    )
    (net (code "125") (name "unconnected-(U1-IO2-Pad24)") (class "Default")
      (node (ref "U1") (pin "24") (pinfunction "IO2_24") (pintype "bidirectional"))
    )
    (net (code "126") (name "unconnected-(U1-IO4-Pad26)") (class "Default")
      (node (ref "U1") (pin "26") (pinfunction "IO4_26") (pintype "bidirectional"))
    )
    (net (code "127") (name "unconnected-(U1-IO12-Pad14)") (class "Default")
      (node (ref "U1") (pin "14") (pinfunction "IO12_14") (pintype "bidirectional"))
    )
    (net (code "128") (name "unconnected-(U1-IO13-Pad16)") (class "Default")
      (node (ref "U1") (pin "16") (pinfunction "IO13_16") (pintype "bidirectional"))
    )
    (net (code "129") (name "unconnected-(U1-IO15-Pad23)") (class "Default")
      (node (ref "U1") (pin "23") (pinfunction "IO15_23") (pintype "bidirectional"))
    )
    (net (code "130") (name "unconnected-(U1-IO16-Pad27)") (class "Default")
      (node (ref "U1") (pin "27") (pinfunction "IO16_27") (pintype "bidirectional"))
    )
    (net (code "131") (name "unconnected-(U1-IO17-Pad28)") (class "Default")
      (node (ref "U1") (pin "28") (pinfunction "IO17_28") (pintype "bidirectional"))
    )
    (net (code "132") (name "unconnected-(U1-IO19-Pad31)") (class "Default")
      (node (ref "U1") (pin "31") (pinfunction "IO19_31") (pintype "bidirectional"))
    )
    (net (code "133") (name "unconnected-(U1-IO32-Pad8)") (class "Default")
      (node (ref "U1") (pin "8") (pinfunction "IO32_8") (pintype "bidirectional"))
    )
    (net (code "134") (name "unconnected-(U1-IO34-Pad6)") (class "Default")
      (node (ref "U1") (pin "6") (pinfunction "IO34_6") (pintype "bidirectional"))
    )
    (net (code "135") (name "unconnected-(U1-IO35-Pad7)") (class "Default")
      (node (ref "U1") (pin "7") (pinfunction "IO35_7") (pintype "bidirectional"))
    )
    (net (code "136") (name "unconnected-(U1-SD0-Pad21)") (class "Default")
      (node (ref "U1") (pin "21") (pinfunction "SD0_21") (pintype "bidirectional"))
    )
    (net (code "137") (name "unconnected-(U1-SD1-Pad22)") (class "Default")
      (node (ref "U1") (pin "22") (pinfunction "SD1_22") (pintype "bidirectional"))
    )
    (net (code "138") (name "unconnected-(U1-SD2-Pad17)") (class "Default")
      (node (ref "U1") (pin "17") (pinfunction "SD2_17") (pintype "bidirectional"))
    )
    (net (code "139") (name "unconnected-(U1-SD3-Pad18)") (class "Default")
      (node (ref "U1") (pin "18") (pinfunction "SD3_18") (pintype "bidirectional"))
    )
    (net (code "140") (name "unconnected-(U1-SVN-Pad5)") (class "Default")
      (node (ref "U1") (pin "5") (pinfunction "SVN_5") (pintype "bidirectional"))
    )
    (net (code "141") (name "unconnected-(U1-SVP-Pad4)") (class "Default")
      (node (ref "U1") (pin "4") (pinfunction "SVP_4") (pintype "bidirectional"))
    )
    (net (code "142") (name "unconnected-(U4-PA02-Pad18)") (class "Default")
      (node (ref "U4") (pin "18") (pinfunction "PA02_18") (pintype "bidirectional"))
    )
    (net (code "143") (name "unconnected-(U4-PA03-Pad19)") (class "Default")
      (node (ref "U4") (pin "19") (pinfunction "PA03_19") (pintype "bidirectional"))
    )
    (net (code "144") (name "unconnected-(U4-PA04-Pad20)") (class "Default")
      (node (ref "U4") (pin "20") (pinfunction "PA04_20") (pintype "bidirectional"))
    )
    (net (code "145") (name "unconnected-(U4-PA05-Pad1)") (class "Default")
      (node (ref "U4") (pin "1") (pinfunction "PA05_1") (pintype "bidirectional"))
    )
    (net (code "146") (name "unconnected-(U4-PA06-Pad2)") (class "Default")
      (node (ref "U4") (pin "2") (pinfunction "PA06_2") (pintype "bidirectional"))
    )
    (net (code "147") (name "unconnected-(U4-PA07-Pad3)") (class "Default")
      (node (ref "U4") (pin "3") (pinfunction "PA07_3") (pintype "bidirectional"))
    )
    (net (code "148") (name "unconnected-(U4-PA08{slash}XIN32-Pad4)") (class "Default")
      (node (ref "U4") (pin "4") (pinfunction "PA08/XIN32_4") (pintype "input"))
    )
    (net (code "149") (name "unconnected-(U4-PA09{slash}XOUT32-Pad5)") (class "Default")
      (node (ref "U4") (pin "5") (pinfunction "PA09/XOUT32_5") (pintype "input"))
    )
    (net (code "150") (name "unconnected-(U4-PA16-Pad8)") (class "Default")
      (node (ref "U4") (pin "8") (pinfunction "PA16_8") (pintype "bidirectional"))
    )
    (net (code "151") (name "unconnected-(U6-2A-Pad5)") (class "Default")
      (node (ref "U6") (pin "5") (pinfunction "2A_5") (pintype "bidirectional"))
    )
    (net (code "152") (name "unconnected-(U6-2Y-Pad4)") (class "Default")
      (node (ref "U6") (pin "4") (pinfunction "2Y_4") (pintype "bidirectional"))
    )
  )
)
